# ventmon_t0_4.net
KiCad netlist of a schematic drawn in EAGLE
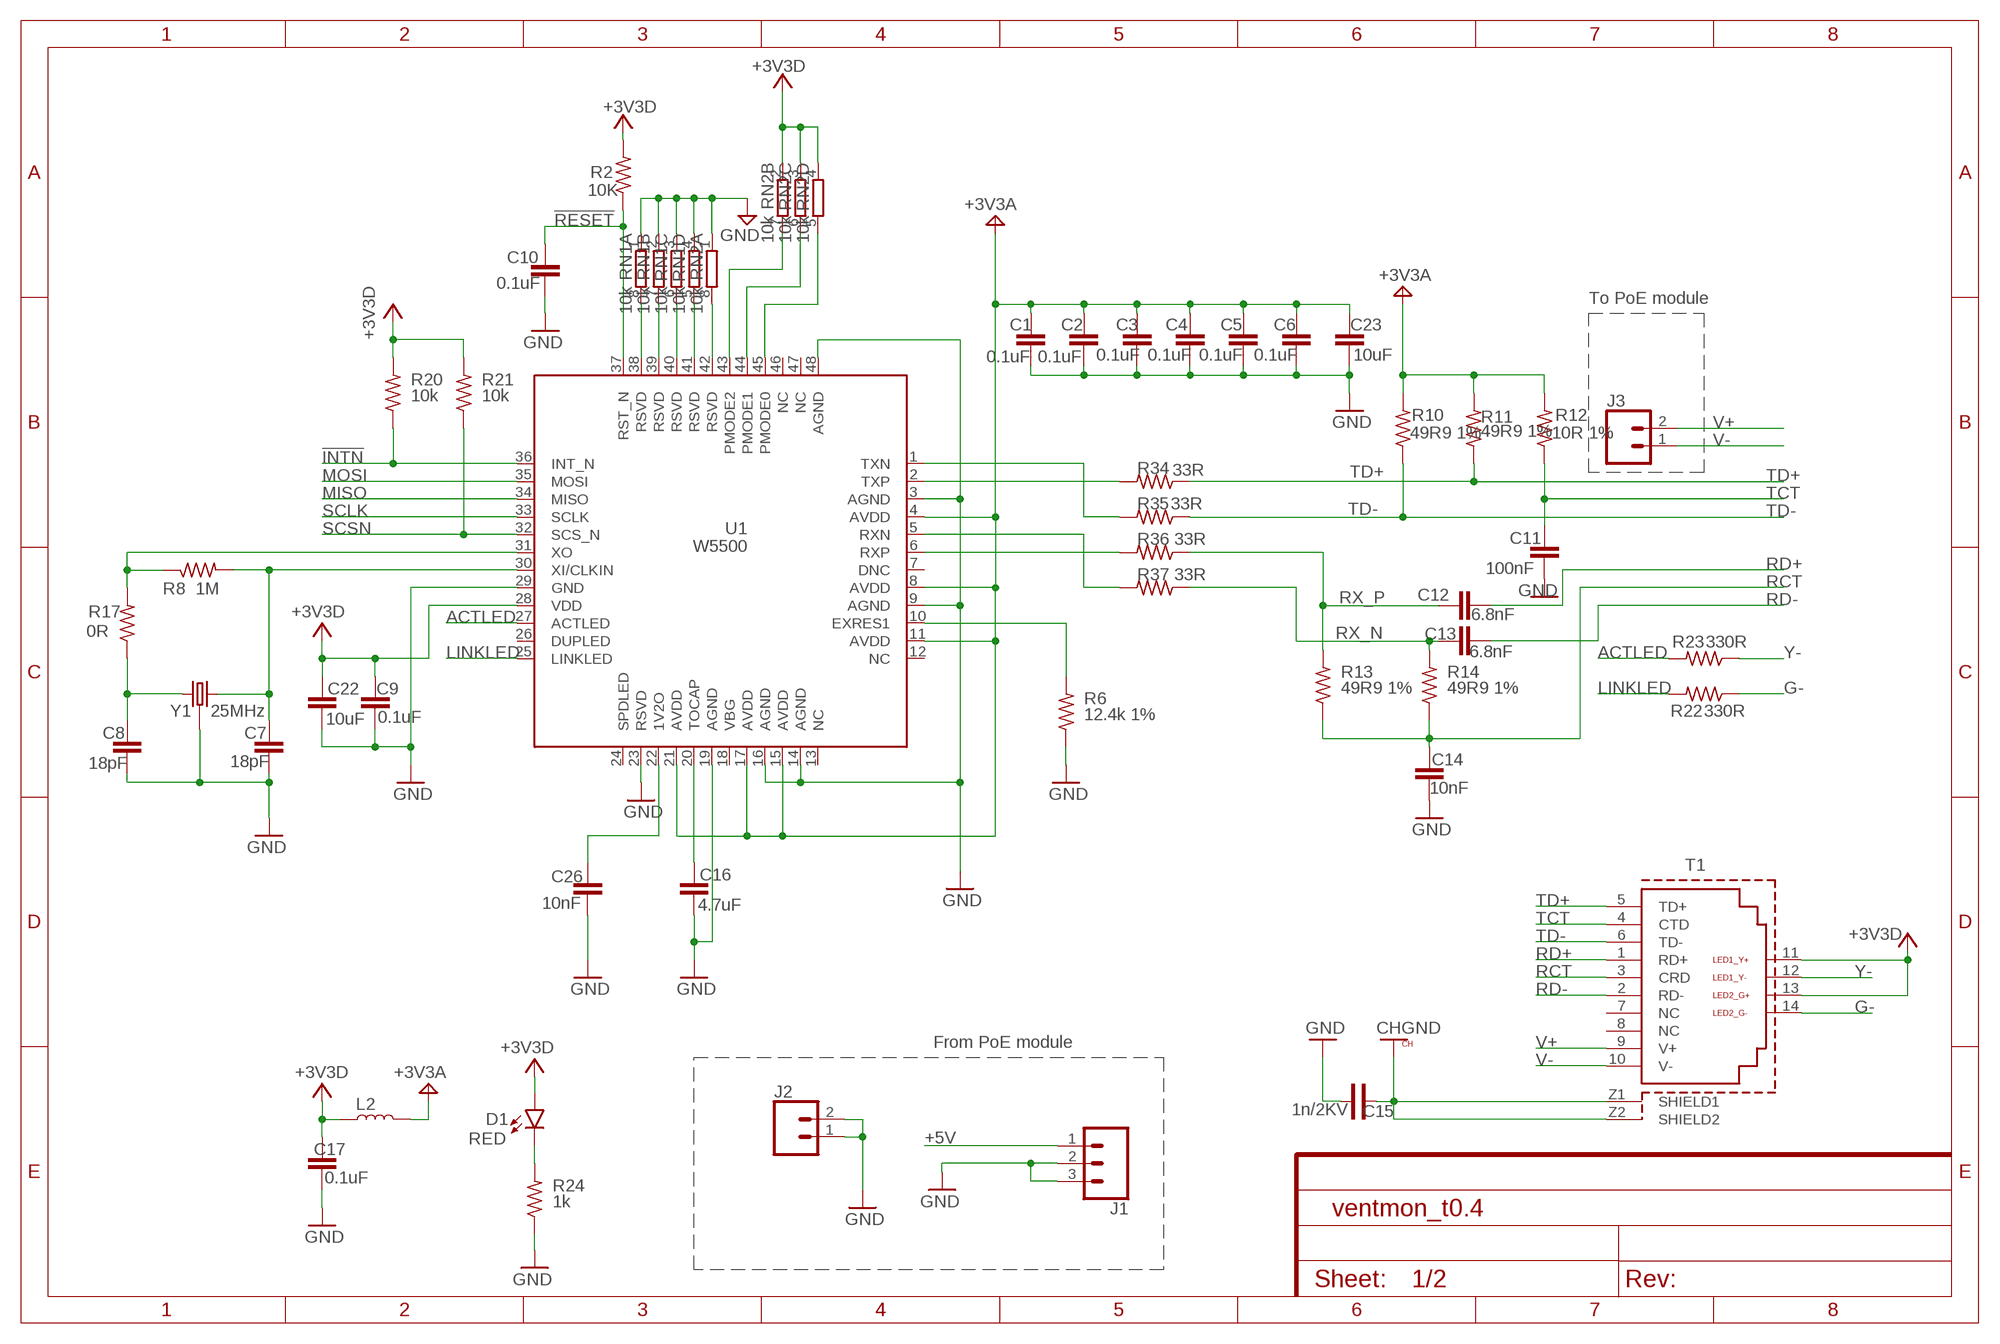
[diagram p0: schematic, sheet 1]
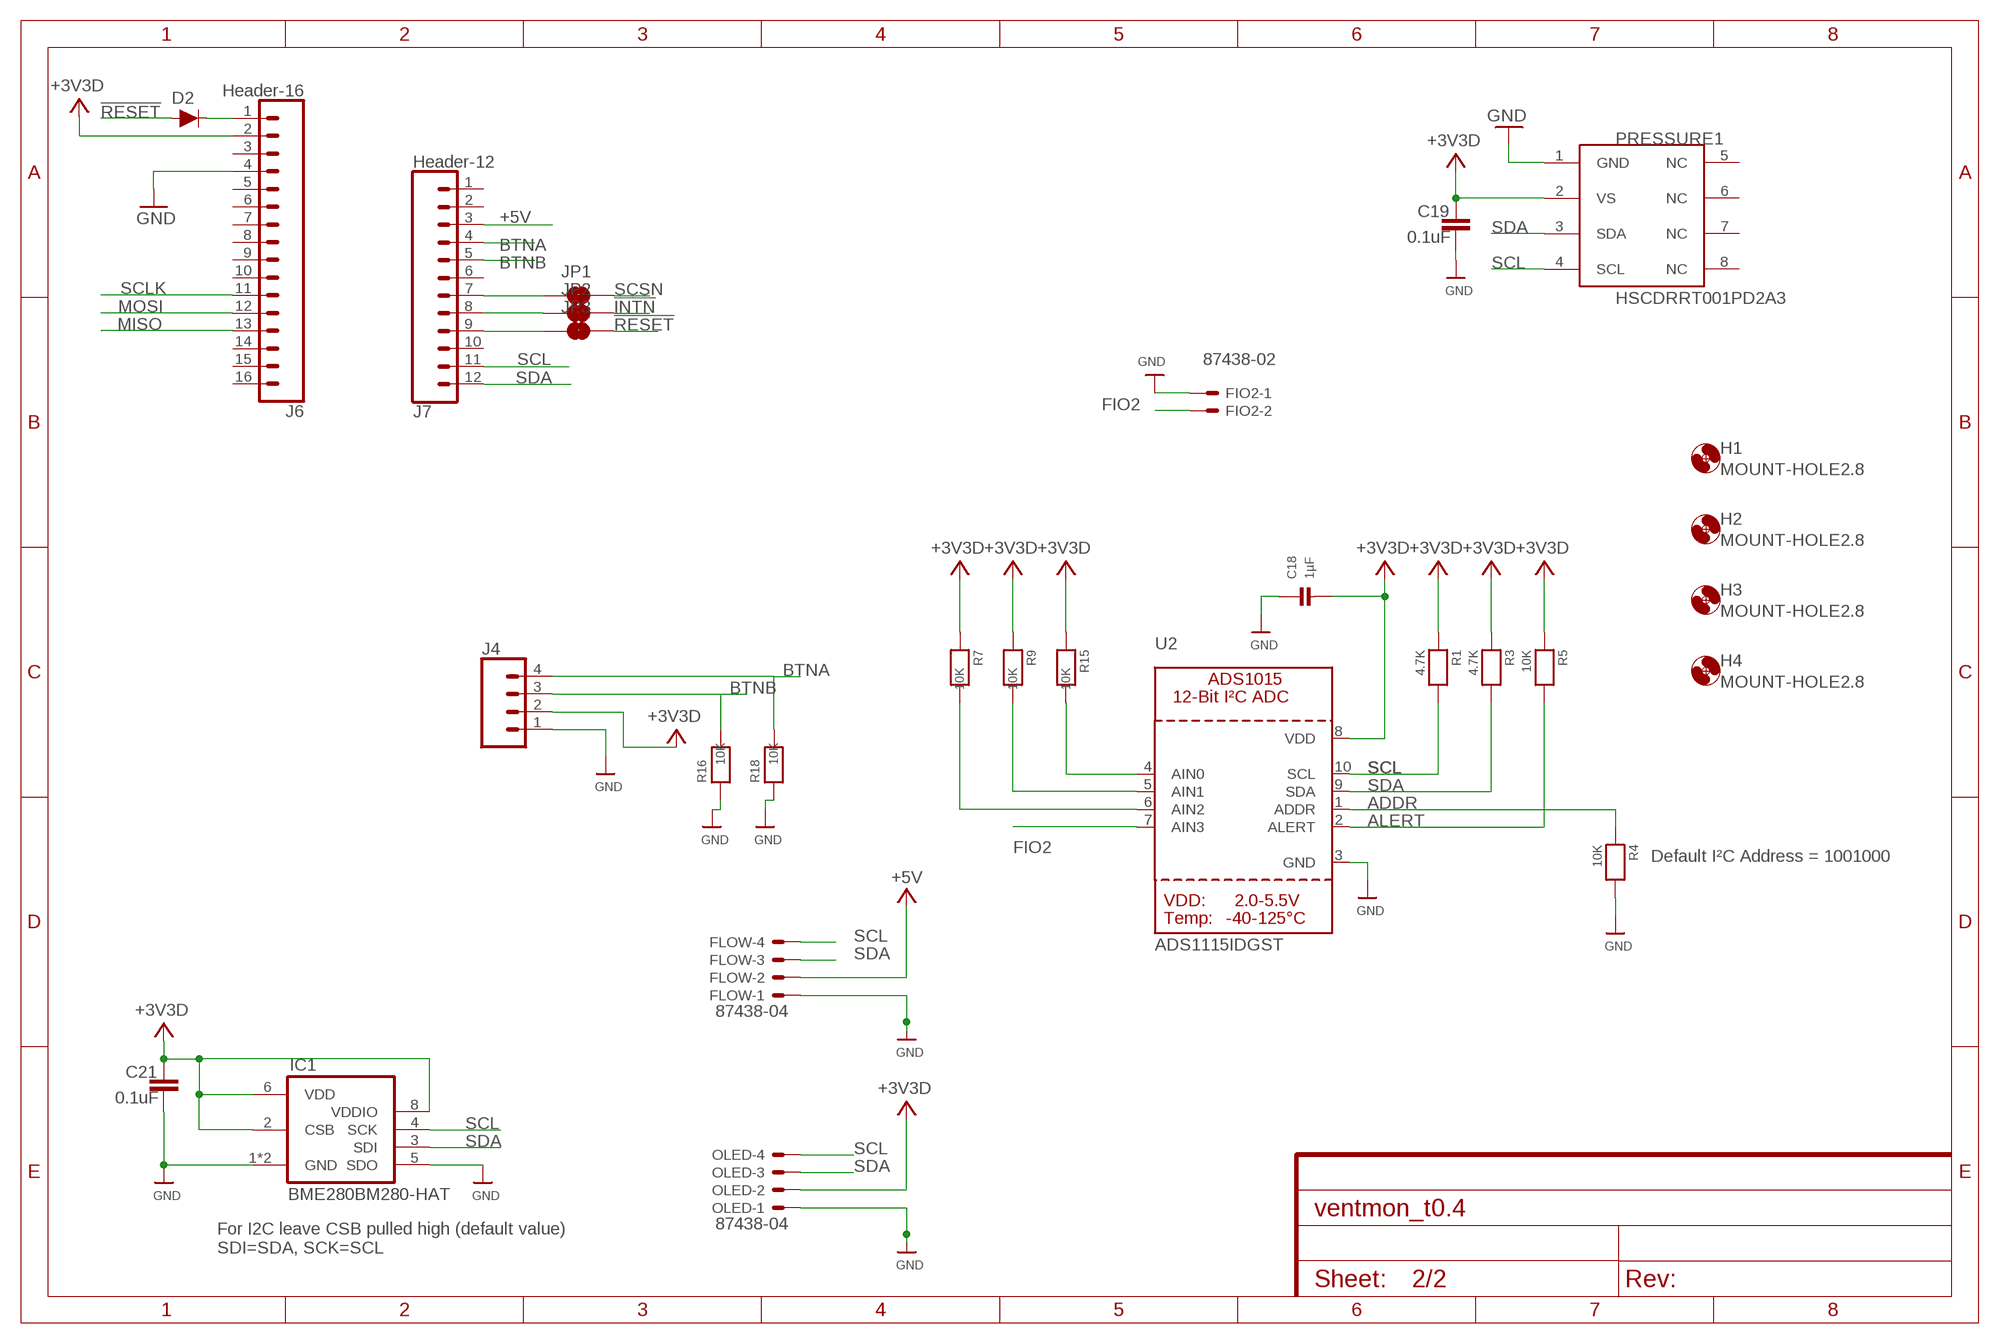
[diagram p1: schematic, sheet 2]

(export (version "E")
  (design (tool "Eeschema 10.0.6"))
  (components
    (comp (ref "C1")
      (value "0.1uF")
      (footprint "eagle-import:C0402_B")
      (libsource (lib "eagle-import") (part "CAP_1"))
    )
    (comp (ref "C2")
      (value "0.1uF")
      (footprint "eagle-import:C0402_B")
      (libsource (lib "eagle-import") (part "CAP_1"))
    )
    (comp (ref "C3")
      (value "0.1uF")
      (footprint "eagle-import:C0402_B")
      (libsource (lib "eagle-import") (part "CAP_1"))
    )
    (comp (ref "C4")
      (value "0.1uF")
      (footprint "eagle-import:C0402_B")
      (libsource (lib "eagle-import") (part "CAP_1"))
    )
    (comp (ref "C5")
      (value "0.1uF")
      (footprint "eagle-import:C0402_B")
      (libsource (lib "eagle-import") (part "CAP_1"))
    )
    (comp (ref "C6")
      (value "0.1uF")
      (footprint "eagle-import:C0402_B")
      (libsource (lib "eagle-import") (part "CAP_1"))
    )
    (comp (ref "C7")
      (value "18pF")
      (footprint "eagle-import:C0402_B")
      (libsource (lib "eagle-import") (part "CAP_1"))
    )
    (comp (ref "C8")
      (value "18pF")
      (footprint "eagle-import:C0402_B")
      (libsource (lib "eagle-import") (part "CAP_1"))
    )
    (comp (ref "C9")
      (value "0.1uF")
      (footprint "eagle-import:C0402_B")
      (libsource (lib "eagle-import") (part "CAP_1"))
    )
    (comp (ref "C10")
      (value "0.1uF")
      (footprint "eagle-import:C0402_B")
      (libsource (lib "eagle-import") (part "CAP_1"))
    )
    (comp (ref "C11")
      (value "100nF")
      (footprint "eagle-import:C0402_B")
      (libsource (lib "eagle-import") (part "CAP_1"))
    )
    (comp (ref "C12")
      (value "6.8nF")
      (footprint "eagle-import:C0402_B")
      (libsource (lib "eagle-import") (part "CAP_1"))
    )
    (comp (ref "C13")
      (value "6.8nF")
      (footprint "eagle-import:C0402_B")
      (libsource (lib "eagle-import") (part "CAP_1"))
    )
    (comp (ref "C14")
      (value "10nF")
      (footprint "eagle-import:C0402_B")
      (libsource (lib "eagle-import") (part "CAP_1"))
    )
    (comp (ref "C15")
      (value "1n/2KV")
      (footprint "eagle-import:C-1808")
      (libsource (lib "eagle-import") (part "C-1808"))
    )
    (comp (ref "C16")
      (value "4.7uF")
      (footprint "eagle-import:0603")
      (libsource (lib "eagle-import") (part "0.18UF-0603-10V-10%"))
    )
    (comp (ref "C17")
      (value "0.1uF")
      (footprint "eagle-import:C0402_B")
      (libsource (lib "eagle-import") (part "CAP_1"))
    )
    (comp (ref "C22")
      (value "10uF")
      (footprint "eagle-import:0603")
      (libsource (lib "eagle-import") (part "0.18UF-0603-10V-10%"))
    )
    (comp (ref "C23")
      (value "10uF")
      (footprint "eagle-import:0603")
      (libsource (lib "eagle-import") (part "0.18UF-0603-10V-10%"))
    )
    (comp (ref "C26")
      (value "10nF")
      (footprint "eagle-import:C0402_B")
      (libsource (lib "eagle-import") (part "CAP_1"))
    )
    (comp (ref "D1")
      (value "RED")
      (footprint "eagle-import:LED-0603")
      (libsource (lib "eagle-import") (part "LED-RED0603"))
    )
    (comp (ref "J1")
      (value "CONN_03")
      (footprint "eagle-import:1X03")
      (libsource (lib "eagle-import") (part "CONN_03"))
    )
    (comp (ref "J2")
      (value "CONN_02")
      (footprint "eagle-import:1X02")
      (libsource (lib "eagle-import") (part "CONN_02"))
    )
    (comp (ref "J3")
      (value "CONN_02")
      (footprint "eagle-import:1X02")
      (libsource (lib "eagle-import") (part "CONN_02"))
    )
    (comp (ref "L2")
      (value "INDUCTOR-0805-3.3UH")
      (footprint "eagle-import:0805")
      (libsource (lib "eagle-import") (part "INDUCTOR-0805-3.3UH"))
    )
    (comp (ref "R2")
      (value "10K")
      (footprint "eagle-import:R0402_B")
      (libsource (lib "eagle-import") (part "R-US_"))
    )
    (comp (ref "R6")
      (value "12.4k 1%")
      (footprint "eagle-import:R0402_B")
      (libsource (lib "eagle-import") (part "R-US_"))
    )
    (comp (ref "R8")
      (value "1M")
      (footprint "eagle-import:R0402_B")
      (libsource (lib "eagle-import") (part "R-US_"))
    )
    (comp (ref "R10")
      (value "49R9 1%")
      (footprint "eagle-import:R0402_B")
      (libsource (lib "eagle-import") (part "R-US_"))
    )
    (comp (ref "R11")
      (value "49R9 1%")
      (footprint "eagle-import:R0402_B")
      (libsource (lib "eagle-import") (part "R-US_"))
    )
    (comp (ref "R12")
      (value "10R 1%")
      (footprint "eagle-import:R0402_B")
      (libsource (lib "eagle-import") (part "R-US_"))
    )
    (comp (ref "R13")
      (value "49R9 1%")
      (footprint "eagle-import:R0402_B")
      (libsource (lib "eagle-import") (part "R-US_"))
    )
    (comp (ref "R14")
      (value "49R9 1%")
      (footprint "eagle-import:R0402_B")
      (libsource (lib "eagle-import") (part "R-US_"))
    )
    (comp (ref "R17")
      (value "0R")
      (footprint "eagle-import:R0402_B")
      (libsource (lib "eagle-import") (part "R-US_"))
    )
    (comp (ref "R20")
      (value "10k")
      (footprint "eagle-import:R0402_B")
      (libsource (lib "eagle-import") (part "R-US_"))
    )
    (comp (ref "R21")
      (value "10k")
      (footprint "eagle-import:R0402_B")
      (libsource (lib "eagle-import") (part "R-US_"))
    )
    (comp (ref "R22")
      (value "330R")
      (footprint "eagle-import:R0402_B")
      (libsource (lib "eagle-import") (part "R-US_"))
    )
    (comp (ref "R23")
      (value "330R")
      (footprint "eagle-import:R0402_B")
      (libsource (lib "eagle-import") (part "R-US_"))
    )
    (comp (ref "R24")
      (value "1k")
      (footprint "eagle-import:R0402_B")
      (libsource (lib "eagle-import") (part "R-US_"))
    )
    (comp (ref "R34")
      (value "33R")
      (footprint "eagle-import:R0402_B")
      (libsource (lib "eagle-import") (part "R-US_"))
    )
    (comp (ref "R35")
      (value "33R")
      (footprint "eagle-import:R0402_B")
      (libsource (lib "eagle-import") (part "R-US_"))
    )
    (comp (ref "R36")
      (value "33R")
      (footprint "eagle-import:R0402_B")
      (libsource (lib "eagle-import") (part "R-US_"))
    )
    (comp (ref "R37")
      (value "33R")
      (footprint "eagle-import:R0402_B")
      (libsource (lib "eagle-import") (part "R-US_"))
    )
    (comp (ref "RN1")
      (value "10k")
      (footprint "eagle-import:4X0402ARV341")
      (libsource (lib "eagle-import") (part "4R-N0402ARV341"))
    )
    (comp (ref "RN2")
      (value "10k")
      (footprint "eagle-import:4X0402ARV341")
      (libsource (lib "eagle-import") (part "4R-N0402ARV341"))
    )
    (comp (ref "T1")
      (value "WE-RJ45_7499210121A")
      (footprint "eagle-import:7499210121A")
      (libsource (lib "eagle-import") (part "WE-RJ45_7499210121A"))
    )
    (comp (ref "U1")
      (value "W5500")
      (footprint "eagle-import:W5500")
      (libsource (lib "eagle-import") (part "W5500"))
    )
    (comp (ref "Y1")
      (value "25MHz")
      (footprint "eagle-import:CRYSTAL-SMD-3.2X2.5MM")
      (libsource (lib "eagle-import") (part "CRYSTAL-GROUNDEDSMD-3.2X2.5"))
    )
    (comp (ref "C18")
      (value "1µF")
      (footprint "eagle-import:0805")
      (libsource (lib "eagle-import") (part "CAP_CERAMIC0805"))
    )
    (comp (ref "C19")
      (value "0.1uF")
      (footprint "eagle-import:C0402_B")
      (libsource (lib "eagle-import") (part "CAP_1"))
    )
    (comp (ref "C21")
      (value "0.1uF")
      (footprint "eagle-import:C0402_B")
      (libsource (lib "eagle-import") (part "CAP_1"))
    )
    (comp (ref "D2")
      (value "DIODE-BAS16J")
      (footprint "eagle-import:SOD-323")
      (libsource (lib "eagle-import") (part "DIODE-BAS16J"))
    )
    (comp (ref "FIO2")
      (value "87438-02")
      (footprint "eagle-import:87438-02")
      (fields (field (name "MF") "MOLEX"))
      (libsource (lib "eagle-import") (part "87438-02"))
    )
    (comp (ref "FLOW")
      (value "87438-04")
      (footprint "eagle-import:87438-04")
      (fields (field (name "MF") "MOLEX"))
      (libsource (lib "eagle-import") (part "87438-04"))
    )
    (comp (ref "H1")
      (value "MOUNT-HOLE2.8")
      (footprint "eagle-import:2,8")
      (libsource (lib "eagle-import") (part "MOUNT-HOLE2.8"))
    )
    (comp (ref "H2")
      (value "MOUNT-HOLE2.8")
      (footprint "eagle-import:2,8")
      (libsource (lib "eagle-import") (part "MOUNT-HOLE2.8"))
    )
    (comp (ref "H3")
      (value "MOUNT-HOLE2.8")
      (footprint "eagle-import:2,8")
      (libsource (lib "eagle-import") (part "MOUNT-HOLE2.8"))
    )
    (comp (ref "H4")
      (value "MOUNT-HOLE2.8")
      (footprint "eagle-import:2,8")
      (libsource (lib "eagle-import") (part "MOUNT-HOLE2.8"))
    )
    (comp (ref "IC1")
      (value "BME280BM280-HAT")
      (footprint "eagle-import:BME280-HAT")
      (libsource (lib "eagle-import") (part "BME280BM280-HAT"))
    )
    (comp (ref "J4")
      (value "CONN_04POLAR")
      (footprint "eagle-import:MOLEX-1X4")
      (libsource (lib "eagle-import") (part "CONN_04POLAR"))
    )
    (comp (ref "J6")
      (value "Header-16")
      (footprint "eagle-import:1X16")
      (libsource (lib "eagle-import") (part "CONN_16"))
    )
    (comp (ref "J7")
      (value "Header-12")
      (footprint "eagle-import:1X12")
      (libsource (lib "eagle-import") (part "CONN_12"))
    )
    (comp (ref "JP1")
      (value "JUMPER-SMT_2_NC_TRACE_NO-SILK")
      (footprint "eagle-import:SMT-JUMPER_2_NC_TRACE_NO-SILK")
      (libsource (lib "eagle-import") (part "JUMPER-SMT_2_NC_TRACE_NO-SILK"))
    )
    (comp (ref "JP2")
      (value "JUMPER-SMT_2_NC_TRACE_NO-SILK")
      (footprint "eagle-import:SMT-JUMPER_2_NC_TRACE_NO-SILK")
      (libsource (lib "eagle-import") (part "JUMPER-SMT_2_NC_TRACE_NO-SILK"))
    )
    (comp (ref "JP3")
      (value "JUMPER-SMT_2_NC_TRACE_NO-SILK")
      (footprint "eagle-import:SMT-JUMPER_2_NC_TRACE_NO-SILK")
      (libsource (lib "eagle-import") (part "JUMPER-SMT_2_NC_TRACE_NO-SILK"))
    )
    (comp (ref "OLED")
      (value "87438-04")
      (footprint "eagle-import:87438-04")
      (fields (field (name "MF") "MOLEX"))
      (libsource (lib "eagle-import") (part "87438-04"))
    )
    (comp (ref "PRESSURE1")
      (value "HSCDRRT001PD2A3")
      (footprint "eagle-import:DIP1330W46P254L1000H616Q8B")
      (libsource (lib "eagle-import") (part "HSCDRRT001PD2A3"))
    )
    (comp (ref "R1")
      (value "4.7K")
      (footprint "eagle-import:0805")
      (libsource (lib "eagle-import") (part "RESISTOR0805"))
    )
    (comp (ref "R3")
      (value "4.7K")
      (footprint "eagle-import:0805")
      (libsource (lib "eagle-import") (part "RESISTOR0805"))
    )
    (comp (ref "R4")
      (value "10K")
      (footprint "eagle-import:0805")
      (libsource (lib "eagle-import") (part "RESISTOR0805"))
    )
    (comp (ref "R5")
      (value "10K")
      (footprint "eagle-import:0805")
      (libsource (lib "eagle-import") (part "RESISTOR0805"))
    )
    (comp (ref "R7")
      (value "10K")
      (footprint "eagle-import:0805")
      (libsource (lib "eagle-import") (part "RESISTOR0805"))
    )
    (comp (ref "R9")
      (value "10K")
      (footprint "eagle-import:0805")
      (libsource (lib "eagle-import") (part "RESISTOR0805"))
    )
    (comp (ref "R15")
      (value "10K")
      (footprint "eagle-import:0805")
      (libsource (lib "eagle-import") (part "RESISTOR0805"))
    )
    (comp (ref "R16")
      (value "10K")
      (footprint "eagle-import:0805")
      (libsource (lib "eagle-import") (part "RESISTOR0805"))
    )
    (comp (ref "R18")
      (value "10K")
      (footprint "eagle-import:0805")
      (libsource (lib "eagle-import") (part "RESISTOR0805"))
    )
    (comp (ref "U2")
      (value "ADS1115IDGST")
      (footprint "eagle-import:MSOP10")
      (libsource (lib "eagle-import") (part "ADC_ADS1015"))
    )
  )
  (nets
    (net (code "1") (name "+3V3") (class "Default")
      (node (ref "C17") (pin "2") (pinfunction "P$2_2") (pintype "passive"))
      (node (ref "C18") (pin "2") (pinfunction "P$2_2") (pintype "passive"))
      (node (ref "C19") (pin "2") (pinfunction "P$2_2") (pintype "passive"))
      (node (ref "C21") (pin "2") (pinfunction "P$2_2") (pintype "passive"))
      (node (ref "C22") (pin "1") (pinfunction "1_1") (pintype "passive"))
      (node (ref "C9") (pin "2") (pinfunction "P$2_2") (pintype "passive"))
      (node (ref "D1") (pin "A") (pinfunction "A_A") (pintype "passive"))
      (node (ref "IC1") (pin "2") (pinfunction "CSB_2") (pintype "input"))
      (node (ref "IC1") (pin "6") (pinfunction "VDD_6") (pintype "power_in"))
      (node (ref "IC1") (pin "8") (pinfunction "VDDIO_8") (pintype "power_in"))
      (node (ref "J4") (pin "2") (pinfunction "2_2") (pintype "passive"))
      (node (ref "J6") (pin "2") (pinfunction "2_2") (pintype "passive"))
      (node (ref "L2") (pin "1") (pinfunction "1_1") (pintype "passive"))
      (node (ref "OLED") (pin "2") (pinfunction "S_2") (pintype "passive"))
      (node (ref "PRESSURE1") (pin "2") (pinfunction "VS_2") (pintype "bidirectional"))
      (node (ref "R1") (pin "1") (pinfunction "1_1") (pintype "passive"))
      (node (ref "R15") (pin "1") (pinfunction "1_1") (pintype "passive"))
      (node (ref "R2") (pin "2") (pinfunction "2_2") (pintype "passive"))
      (node (ref "R20") (pin "2") (pinfunction "2_2") (pintype "passive"))
      (node (ref "R21") (pin "2") (pinfunction "2_2") (pintype "passive"))
      (node (ref "R3") (pin "1") (pinfunction "1_1") (pintype "passive"))
      (node (ref "R5") (pin "1") (pinfunction "1_1") (pintype "passive"))
      (node (ref "R7") (pin "1") (pinfunction "1_1") (pintype "passive"))
      (node (ref "R9") (pin "1") (pinfunction "1_1") (pintype "passive"))
      (node (ref "RN2") (pin "2") (pinfunction "1_2") (pintype "passive"))
      (node (ref "RN2") (pin "3") (pinfunction "1_3") (pintype "passive"))
      (node (ref "RN2") (pin "4") (pinfunction "1_4") (pintype "passive"))
      (node (ref "T1") (pin "11") (pinfunction "LED1_Y+_11") (pintype "passive"))
      (node (ref "T1") (pin "13") (pinfunction "LED2_G+_13") (pintype "passive"))
      (node (ref "U1") (pin "28") (pinfunction "VDD_28") (pintype "passive"))
      (node (ref "U2") (pin "8") (pinfunction "VDD_8") (pintype "bidirectional"))
    )
    (net (code "2") (name "+3V3A") (class "Default")
      (node (ref "C1") (pin "2") (pinfunction "P$2_2") (pintype "passive"))
      (node (ref "C2") (pin "2") (pinfunction "P$2_2") (pintype "passive"))
      (node (ref "C23") (pin "1") (pinfunction "1_1") (pintype "passive"))
      (node (ref "C3") (pin "2") (pinfunction "P$2_2") (pintype "passive"))
      (node (ref "C4") (pin "2") (pinfunction "P$2_2") (pintype "passive"))
      (node (ref "C5") (pin "2") (pinfunction "P$2_2") (pintype "passive"))
      (node (ref "C6") (pin "2") (pinfunction "P$2_2") (pintype "passive"))
      (node (ref "L2") (pin "2") (pinfunction "2_2") (pintype "passive"))
      (node (ref "R10") (pin "2") (pinfunction "2_2") (pintype "passive"))
      (node (ref "R11") (pin "2") (pinfunction "2_2") (pintype "passive"))
      (node (ref "R12") (pin "2") (pinfunction "2_2") (pintype "passive"))
      (node (ref "U1") (pin "11") (pinfunction "AVDD_11") (pintype "passive"))
      (node (ref "U1") (pin "15") (pinfunction "AVDD_15") (pintype "passive"))
      (node (ref "U1") (pin "17") (pinfunction "AVDD_17") (pintype "passive"))
      (node (ref "U1") (pin "21") (pinfunction "AVDD_21") (pintype "passive"))
      (node (ref "U1") (pin "4") (pinfunction "AVDD_4") (pintype "passive"))
      (node (ref "U1") (pin "8") (pinfunction "AVDD_8") (pintype "passive"))
    )
    (net (code "3") (name "+5V") (class "Default")
      (node (ref "FLOW") (pin "2") (pinfunction "S_2") (pintype "passive"))
      (node (ref "J1") (pin "1") (pinfunction "1_1") (pintype "passive"))
      (node (ref "J7") (pin "3") (pinfunction "3_3") (pintype "passive"))
    )
    (net (code "4") (name "ACTLED") (class "Default")
      (node (ref "R23") (pin "2") (pinfunction "2_2") (pintype "passive"))
      (node (ref "U1") (pin "27") (pinfunction "ACTLED_27") (pintype "passive"))
    )
    (net (code "5") (name "ADDR") (class "Default")
      (node (ref "R4") (pin "1") (pinfunction "1_1") (pintype "passive"))
      (node (ref "U2") (pin "1") (pinfunction "ADDR_1") (pintype "bidirectional"))
    )
    (net (code "6") (name "ALERT") (class "Default")
      (node (ref "R5") (pin "2") (pinfunction "2_2") (pintype "passive"))
      (node (ref "U2") (pin "2") (pinfunction "ALERT_2") (pintype "bidirectional"))
    )
    (net (code "7") (name "BTNA") (class "Default")
      (node (ref "J4") (pin "4") (pinfunction "4_4") (pintype "passive"))
      (node (ref "J7") (pin "4") (pinfunction "4_4") (pintype "passive"))
      (node (ref "R18") (pin "2") (pinfunction "2_2") (pintype "passive"))
    )
    (net (code "8") (name "BTNB") (class "Default")
      (node (ref "J4") (pin "3") (pinfunction "3_3") (pintype "passive"))
      (node (ref "J7") (pin "5") (pinfunction "5_5") (pintype "passive"))
      (node (ref "R16") (pin "2") (pinfunction "2_2") (pintype "passive"))
    )
    (net (code "9") (name "CHGND") (class "Default")
      (node (ref "C15") (pin "P$1") (pinfunction "P$1_P$1") (pintype "passive"))
      (node (ref "T1") (pin "Z1") (pinfunction "SHIELD1_Z1") (pintype "power_in"))
      (node (ref "T1") (pin "Z2") (pinfunction "SHIELD2_Z2") (pintype "power_in"))
    )
    (net (code "10") (name "FIO2") (class "Default")
      (node (ref "FIO2") (pin "2") (pinfunction "S_2") (pintype "passive"))
      (node (ref "U2") (pin "7") (pinfunction "AIN3_7") (pintype "bidirectional"))
    )
    (net (code "11") (name "G-") (class "Default")
      (node (ref "R22") (pin "1") (pinfunction "1_1") (pintype "passive"))
      (node (ref "T1") (pin "14") (pinfunction "LED2_G-_14") (pintype "passive"))
    )
    (net (code "12") (name "GND") (class "Default")
      (node (ref "C1") (pin "1") (pinfunction "P$1_1") (pintype "passive"))
      (node (ref "C10") (pin "1") (pinfunction "P$1_1") (pintype "passive"))
      (node (ref "C11") (pin "1") (pinfunction "P$1_1") (pintype "passive"))
      (node (ref "C14") (pin "1") (pinfunction "P$1_1") (pintype "passive"))
      (node (ref "C15") (pin "P$2") (pinfunction "P$2_P$2") (pintype "passive"))
      (node (ref "C16") (pin "2") (pinfunction "2_2") (pintype "passive"))
      (node (ref "C17") (pin "1") (pinfunction "P$1_1") (pintype "passive"))
      (node (ref "C18") (pin "1") (pinfunction "P$1_1") (pintype "passive"))
      (node (ref "C19") (pin "1") (pinfunction "P$1_1") (pintype "passive"))
      (node (ref "C2") (pin "1") (pinfunction "P$1_1") (pintype "passive"))
      (node (ref "C21") (pin "1") (pinfunction "P$1_1") (pintype "passive"))
      (node (ref "C22") (pin "2") (pinfunction "2_2") (pintype "passive"))
      (node (ref "C23") (pin "2") (pinfunction "2_2") (pintype "passive"))
      (node (ref "C26") (pin "1") (pinfunction "P$1_1") (pintype "passive"))
      (node (ref "C3") (pin "1") (pinfunction "P$1_1") (pintype "passive"))
      (node (ref "C4") (pin "1") (pinfunction "P$1_1") (pintype "passive"))
      (node (ref "C5") (pin "1") (pinfunction "P$1_1") (pintype "passive"))
      (node (ref "C6") (pin "1") (pinfunction "P$1_1") (pintype "passive"))
      (node (ref "C7") (pin "1") (pinfunction "P$1_1") (pintype "passive"))
      (node (ref "C8") (pin "1") (pinfunction "P$1_1") (pintype "passive"))
      (node (ref "C9") (pin "1") (pinfunction "P$1_1") (pintype "passive"))
      (node (ref "FIO2") (pin "1") (pinfunction "S_1") (pintype "passive"))
      (node (ref "FLOW") (pin "1") (pinfunction "S_1") (pintype "passive"))
      (node (ref "IC1") (pin "1") (pinfunction "GND_1") (pintype "power_in"))
      (node (ref "IC1") (pin "5") (pinfunction "SDO_5") (pintype "input"))
      (node (ref "IC1") (pin "7") (pinfunction "GND_7") (pintype "power_in"))
      (node (ref "J1") (pin "2") (pinfunction "2_2") (pintype "passive"))
      (node (ref "J1") (pin "3") (pinfunction "3_3") (pintype "passive"))
      (node (ref "J2") (pin "1") (pinfunction "1_1") (pintype "passive"))
      (node (ref "J2") (pin "2") (pinfunction "2_2") (pintype "passive"))
      (node (ref "J4") (pin "1") (pinfunction "1_1") (pintype "passive"))
      (node (ref "J6") (pin "4") (pinfunction "4_4") (pintype "passive"))
      (node (ref "OLED") (pin "1") (pinfunction "S_1") (pintype "passive"))
      (node (ref "PRESSURE1") (pin "1") (pinfunction "GND_1") (pintype "bidirectional"))
      (node (ref "R16") (pin "1") (pinfunction "1_1") (pintype "passive"))
      (node (ref "R18") (pin "1") (pinfunction "1_1") (pintype "passive"))
      (node (ref "R24") (pin "1") (pinfunction "1_1") (pintype "passive"))
      (node (ref "R4") (pin "2") (pinfunction "2_2") (pintype "passive"))
      (node (ref "R6") (pin "1") (pinfunction "1_1") (pintype "passive"))
      (node (ref "RN1") (pin "1") (pinfunction "1_1") (pintype "passive"))
      (node (ref "RN1") (pin "2") (pinfunction "1_2") (pintype "passive"))
      (node (ref "RN1") (pin "3") (pinfunction "1_3") (pintype "passive"))
      (node (ref "RN1") (pin "4") (pinfunction "1_4") (pintype "passive"))
      (node (ref "RN2") (pin "1") (pinfunction "1_1") (pintype "passive"))
      (node (ref "U1") (pin "14") (pinfunction "AGND_14") (pintype "passive"))
      (node (ref "U1") (pin "16") (pinfunction "AGND_16") (pintype "passive"))
      (node (ref "U1") (pin "19") (pinfunction "AGND_19") (pintype "passive"))
      (node (ref "U1") (pin "23") (pinfunction "RSVD_23") (pintype "passive"))
      (node (ref "U1") (pin "29") (pinfunction "GND_29") (pintype "passive"))
      (node (ref "U1") (pin "3") (pinfunction "AGND_3") (pintype "passive"))
      (node (ref "U1") (pin "48") (pinfunction "AGND_48") (pintype "passive"))
      (node (ref "U1") (pin "9") (pinfunction "AGND_9") (pintype "passive"))
      (node (ref "U2") (pin "3") (pinfunction "GND_3") (pintype "bidirectional"))
      (node (ref "Y1") (pin "2") (pinfunction "3_2") (pintype "passive"))
      (node (ref "Y1") (pin "4") (pinfunction "3_4") (pintype "passive"))
    )
    (net (code "13") (name "LINKLED") (class "Default")
      (node (ref "R22") (pin "2") (pinfunction "2_2") (pintype "passive"))
      (node (ref "U1") (pin "25") (pinfunction "LINKLED_25") (pintype "passive"))
    )
    (net (code "14") (name "MISO") (class "Default")
      (node (ref "J6") (pin "13") (pinfunction "13_13") (pintype "passive"))
      (node (ref "U1") (pin "34") (pinfunction "MISO_34") (pintype "passive"))
    )
    (net (code "15") (name "MOSI") (class "Default")
      (node (ref "J6") (pin "12") (pinfunction "12_12") (pintype "passive"))
      (node (ref "U1") (pin "35") (pinfunction "MOSI_35") (pintype "passive"))
    )
    (net (code "16") (name "Net-(C7-P$2)") (class "Default")
      (node (ref "C7") (pin "2") (pinfunction "P$2_2") (pintype "passive"))
      (node (ref "R8") (pin "2") (pinfunction "2_2") (pintype "passive"))
      (node (ref "U1") (pin "30") (pinfunction "XI/CLKIN_30") (pintype "passive"))
      (node (ref "Y1") (pin "3") (pinfunction "2_3") (pintype "passive"))
    )
    (net (code "17") (name "Net-(C8-P$2)") (class "Default")
      (node (ref "C8") (pin "2") (pinfunction "P$2_2") (pintype "passive"))
      (node (ref "R17") (pin "1") (pinfunction "1_1") (pintype "passive"))
      (node (ref "Y1") (pin "1") (pinfunction "1_1") (pintype "passive"))
    )
    (net (code "18") (name "Net-(C26-P$2)") (class "Default")
      (node (ref "C26") (pin "2") (pinfunction "P$2_2") (pintype "passive"))
      (node (ref "U1") (pin "22") (pinfunction "1V2O_22") (pintype "passive"))
    )
    (net (code "19") (name "Net-(D1-PadC)") (class "Default")
      (node (ref "D1") (pin "C") (pinfunction "C_C") (pintype "passive"))
      (node (ref "R24") (pin "2") (pinfunction "2_2") (pintype "passive"))
    )
    (net (code "20") (name "Net-(D2-PadC)") (class "Default")
      (node (ref "D2") (pin "C") (pinfunction "C_C") (pintype "passive"))
      (node (ref "J6") (pin "1") (pinfunction "1_1") (pintype "passive"))
    )
    (net (code "21") (name "Net-(J7-Pad7)") (class "Default")
      (node (ref "J7") (pin "7") (pinfunction "7_7") (pintype "passive"))
      (node (ref "JP1") (pin "1") (pinfunction "1_1") (pintype "passive"))
    )
    (net (code "22") (name "Net-(J7-Pad8)") (class "Default")
      (node (ref "J7") (pin "8") (pinfunction "8_8") (pintype "passive"))
      (node (ref "JP2") (pin "1") (pinfunction "1_1") (pintype "passive"))
    )
    (net (code "23") (name "Net-(J7-Pad9)") (class "Default")
      (node (ref "J7") (pin "9") (pinfunction "9_9") (pintype "passive"))
      (node (ref "JP3") (pin "1") (pinfunction "1_1") (pintype "passive"))
    )
    (net (code "24") (name "Net-(RN1A-2)") (class "Default")
      (node (ref "RN1") (pin "8") (pinfunction "2_8") (pintype "passive"))
      (node (ref "U1") (pin "38") (pinfunction "RSVD_38") (pintype "passive"))
    )
    (net (code "25") (name "Net-(RN1B-2)") (class "Default")
      (node (ref "RN1") (pin "7") (pinfunction "2_7") (pintype "passive"))
      (node (ref "U1") (pin "39") (pinfunction "RSVD_39") (pintype "passive"))
    )
    (net (code "26") (name "Net-(RN1C-2)") (class "Default")
      (node (ref "RN1") (pin "6") (pinfunction "2_6") (pintype "passive"))
      (node (ref "U1") (pin "40") (pinfunction "RSVD_40") (pintype "passive"))
    )
    (net (code "27") (name "Net-(RN1D-2)") (class "Default")
      (node (ref "RN1") (pin "5") (pinfunction "2_5") (pintype "passive"))
      (node (ref "U1") (pin "41") (pinfunction "RSVD_41") (pintype "passive"))
    )
    (net (code "28") (name "Net-(RN2A-2)") (class "Default")
      (node (ref "RN2") (pin "8") (pinfunction "2_8") (pintype "passive"))
      (node (ref "U1") (pin "42") (pinfunction "RSVD_42") (pintype "passive"))
    )
    (net (code "29") (name "Net-(RN2B-2)") (class "Default")
      (node (ref "RN2") (pin "7") (pinfunction "2_7") (pintype "passive"))
      (node (ref "U1") (pin "43") (pinfunction "PMODE2_43") (pintype "passive"))
    )
    (net (code "30") (name "Net-(RN2C-2)") (class "Default")
      (node (ref "RN2") (pin "6") (pinfunction "2_6") (pintype "passive"))
      (node (ref "U1") (pin "44") (pinfunction "PMODE1_44") (pintype "passive"))
    )
    (net (code "31") (name "Net-(RN2D-2)") (class "Default")
      (node (ref "RN2") (pin "5") (pinfunction "2_5") (pintype "passive"))
      (node (ref "U1") (pin "45") (pinfunction "PMODE0_45") (pintype "passive"))
    )
    (net (code "32") (name "Net-(U1-EXRES1)") (class "Default")
      (node (ref "R6") (pin "2") (pinfunction "2_2") (pintype "passive"))
      (node (ref "U1") (pin "10") (pinfunction "EXRES1_10") (pintype "passive"))
    )
    (net (code "33") (name "Net-(U1-RXN)") (class "Default")
      (node (ref "R37") (pin "2") (pinfunction "2_2") (pintype "passive"))
      (node (ref "U1") (pin "5") (pinfunction "RXN_5") (pintype "passive"))
    )
    (net (code "34") (name "Net-(U1-RXP)") (class "Default")
      (node (ref "R36") (pin "2") (pinfunction "2_2") (pintype "passive"))
      (node (ref "U1") (pin "6") (pinfunction "RXP_6") (pintype "passive"))
    )
    (net (code "35") (name "Net-(U1-TOCAP)") (class "Default")
      (node (ref "C16") (pin "1") (pinfunction "1_1") (pintype "passive"))
      (node (ref "U1") (pin "20") (pinfunction "TOCAP_20") (pintype "passive"))
    )
    (net (code "36") (name "Net-(U1-TXN)") (class "Default")
      (node (ref "R35") (pin "2") (pinfunction "2_2") (pintype "passive"))
      (node (ref "U1") (pin "1") (pinfunction "TXN_1") (pintype "passive"))
    )
    (net (code "37") (name "Net-(U1-TXP)") (class "Default")
      (node (ref "R34") (pin "2") (pinfunction "2_2") (pintype "passive"))
      (node (ref "U1") (pin "2") (pinfunction "TXP_2") (pintype "passive"))
    )
    (net (code "38") (name "Net-(U1-XO)") (class "Default")
      (node (ref "R17") (pin "2") (pinfunction "2_2") (pintype "passive"))
      (node (ref "R8") (pin "1") (pinfunction "1_1") (pintype "passive"))
      (node (ref "U1") (pin "31") (pinfunction "XO_31") (pintype "passive"))
    )
    (net (code "39") (name "Net-(U2-AIN0)") (class "Default")
      (node (ref "R15") (pin "2") (pinfunction "2_2") (pintype "passive"))
      (node (ref "U2") (pin "4") (pinfunction "AIN0_4") (pintype "bidirectional"))
    )
    (net (code "40") (name "Net-(U2-AIN1)") (class "Default")
      (node (ref "R9") (pin "2") (pinfunction "2_2") (pintype "passive"))
      (node (ref "U2") (pin "5") (pinfunction "AIN1_5") (pintype "bidirectional"))
    )
    (net (code "41") (name "Net-(U2-AIN2)") (class "Default")
      (node (ref "R7") (pin "2") (pinfunction "2_2") (pintype "passive"))
      (node (ref "U2") (pin "6") (pinfunction "AIN2_6") (pintype "bidirectional"))
    )
    (net (code "42") (name "RCT") (class "Default")
      (node (ref "C14") (pin "2") (pinfunction "P$2_2") (pintype "passive"))
      (node (ref "R13") (pin "1") (pinfunction "1_1") (pintype "passive"))
      (node (ref "R14") (pin "1") (pinfunction "1_1") (pintype "passive"))
      (node (ref "T1") (pin "3") (pinfunction "CRD_3") (pintype "bidirectional"))
    )
    (net (code "43") (name "RD+") (class "Default")
      (node (ref "C12") (pin "2") (pinfunction "P$2_2") (pintype "passive"))
      (node (ref "T1") (pin "1") (pinfunction "RD+_1") (pintype "bidirectional"))
    )
    (net (code "44") (name "RD-") (class "Default")
      (node (ref "C13") (pin "2") (pinfunction "P$2_2") (pintype "passive"))
      (node (ref "T1") (pin "2") (pinfunction "RD-_2") (pintype "bidirectional"))
    )
    (net (code "45") (name "RX_N") (class "Default")
      (node (ref "C13") (pin "1") (pinfunction "P$1_1") (pintype "passive"))
      (node (ref "R14") (pin "2") (pinfunction "2_2") (pintype "passive"))
      (node (ref "R37") (pin "1") (pinfunction "1_1") (pintype "passive"))
    )
    (net (code "46") (name "RX_P") (class "Default")
      (node (ref "C12") (pin "1") (pinfunction "P$1_1") (pintype "passive"))
      (node (ref "R13") (pin "2") (pinfunction "2_2") (pintype "passive"))
      (node (ref "R36") (pin "1") (pinfunction "1_1") (pintype "passive"))
    )
    (net (code "47") (name "SCL") (class "Default")
      (node (ref "FLOW") (pin "4") (pinfunction "S_4") (pintype "passive"))
      (node (ref "IC1") (pin "4") (pinfunction "SCK_4") (pintype "bidirectional"))
      (node (ref "J7") (pin "11") (pinfunction "11_11") (pintype "passive"))
      (node (ref "OLED") (pin "4") (pinfunction "S_4") (pintype "passive"))
      (node (ref "PRESSURE1") (pin "4") (pinfunction "SCL_4") (pintype "bidirectional"))
      (node (ref "R1") (pin "2") (pinfunction "2_2") (pintype "passive"))
      (node (ref "U2") (pin "10") (pinfunction "SCL_10") (pintype "bidirectional"))
    )
    (net (code "48") (name "SCLK") (class "Default")
      (node (ref "J6") (pin "11") (pinfunction "11_11") (pintype "passive"))
      (node (ref "U1") (pin "33") (pinfunction "SCLK_33") (pintype "passive"))
    )
    (net (code "49") (name "SCSN") (class "Default")
      (node (ref "JP1") (pin "2") (pinfunction "2_2") (pintype "passive"))
      (node (ref "R21") (pin "1") (pinfunction "1_1") (pintype "passive"))
      (node (ref "U1") (pin "32") (pinfunction "SCS_N_32") (pintype "passive"))
    )
    (net (code "50") (name "SDA") (class "Default")
      (node (ref "FLOW") (pin "3") (pinfunction "S_3") (pintype "passive"))
      (node (ref "IC1") (pin "3") (pinfunction "SDI_3") (pintype "bidirectional"))
      (node (ref "J7") (pin "12") (pinfunction "12_12") (pintype "passive"))
      (node (ref "OLED") (pin "3") (pinfunction "S_3") (pintype "passive"))
      (node (ref "PRESSURE1") (pin "3") (pinfunction "SDA_3") (pintype "bidirectional"))
      (node (ref "R3") (pin "2") (pinfunction "2_2") (pintype "passive"))
      (node (ref "U2") (pin "9") (pinfunction "SDA_9") (pintype "bidirectional"))
    )
    (net (code "51") (name "TCT") (class "Default")
      (node (ref "C11") (pin "2") (pinfunction "P$2_2") (pintype "passive"))
      (node (ref "R12") (pin "1") (pinfunction "1_1") (pintype "passive"))
      (node (ref "T1") (pin "4") (pinfunction "CTD_4") (pintype "bidirectional"))
    )
    (net (code "52") (name "TD+") (class "Default")
      (node (ref "R11") (pin "1") (pinfunction "1_1") (pintype "passive"))
      (node (ref "R34") (pin "1") (pinfunction "1_1") (pintype "passive"))
      (node (ref "T1") (pin "5") (pinfunction "TD+_5") (pintype "bidirectional"))
    )
    (net (code "53") (name "TD-") (class "Default")
      (node (ref "R10") (pin "1") (pinfunction "1_1") (pintype "passive"))
      (node (ref "R35") (pin "1") (pinfunction "1_1") (pintype "passive"))
      (node (ref "T1") (pin "6") (pinfunction "TD-_6") (pintype "bidirectional"))
    )
    (net (code "54") (name "V+") (class "Default")
      (node (ref "J3") (pin "2") (pinfunction "2_2") (pintype "passive"))
      (node (ref "T1") (pin "9") (pinfunction "V+_9") (pintype "bidirectional"))
    )
    (net (code "55") (name "V-") (class "Default")
      (node (ref "J3") (pin "1") (pinfunction "1_1") (pintype "passive"))
      (node (ref "T1") (pin "10") (pinfunction "V-_10") (pintype "bidirectional"))
    )
    (net (code "56") (name "Y-") (class "Default")
      (node (ref "R23") (pin "1") (pinfunction "1_1") (pintype "passive"))
      (node (ref "T1") (pin "12") (pinfunction "LED1_Y-_12") (pintype "passive"))
    )
    (net (code "57") (name "unconnected-(J6-Pad3)") (class "Default")
      (node (ref "J6") (pin "3") (pinfunction "3_3") (pintype "passive"))
    )
    (net (code "58") (name "unconnected-(J6-Pad5)") (class "Default")
      (node (ref "J6") (pin "5") (pinfunction "5_5") (pintype "passive"))
    )
    (net (code "59") (name "unconnected-(J6-Pad6)") (class "Default")
      (node (ref "J6") (pin "6") (pinfunction "6_6") (pintype "passive"))
    )
    (net (code "60") (name "unconnected-(J6-Pad7)") (class "Default")
      (node (ref "J6") (pin "7") (pinfunction "7_7") (pintype "passive"))
    )
    (net (code "61") (name "unconnected-(J6-Pad8)") (class "Default")
      (node (ref "J6") (pin "8") (pinfunction "8_8") (pintype "passive"))
    )
    (net (code "62") (name "unconnected-(J6-Pad9)") (class "Default")
      (node (ref "J6") (pin "9") (pinfunction "9_9") (pintype "passive"))
    )
    (net (code "63") (name "unconnected-(J6-Pad10)") (class "Default")
      (node (ref "J6") (pin "10") (pinfunction "10_10") (pintype "passive"))
    )
    (net (code "64") (name "unconnected-(J6-Pad14)") (class "Default")
      (node (ref "J6") (pin "14") (pinfunction "14_14") (pintype "passive"))
    )
    (net (code "65") (name "unconnected-(J6-Pad15)") (class "Default")
      (node (ref "J6") (pin "15") (pinfunction "15_15") (pintype "passive"))
    )
    (net (code "66") (name "unconnected-(J6-Pad16)") (class "Default")
      (node (ref "J6") (pin "16") (pinfunction "16_16") (pintype "passive"))
    )
    (net (code "67") (name "unconnected-(J7-Pad1)") (class "Default")
      (node (ref "J7") (pin "1") (pinfunction "1_1") (pintype "passive"))
    )
    (net (code "68") (name "unconnected-(J7-Pad2)") (class "Default")
      (node (ref "J7") (pin "2") (pinfunction "2_2") (pintype "passive"))
    )
    (net (code "69") (name "unconnected-(J7-Pad6)") (class "Default")
      (node (ref "J7") (pin "6") (pinfunction "6_6") (pintype "passive"))
    )
    (net (code "70") (name "unconnected-(J7-Pad10)") (class "Default")
      (node (ref "J7") (pin "10") (pinfunction "10_10") (pintype "passive"))
    )
    (net (code "71") (name "unconnected-(PRESSURE1-NC-Pad5)") (class "Default")
      (node (ref "PRESSURE1") (pin "5") (pinfunction "NC_5") (pintype "bidirectional"))
    )
    (net (code "72") (name "unconnected-(PRESSURE1-NC-Pad6)") (class "Default")
      (node (ref "PRESSURE1") (pin "6") (pinfunction "NC_6") (pintype "bidirectional"))
    )
    (net (code "73") (name "unconnected-(PRESSURE1-NC-Pad7)") (class "Default")
      (node (ref "PRESSURE1") (pin "7") (pinfunction "NC_7") (pintype "bidirectional"))
    )
    (net (code "74") (name "unconnected-(PRESSURE1-NC-Pad8)") (class "Default")
      (node (ref "PRESSURE1") (pin "8") (pinfunction "NC_8") (pintype "bidirectional"))
    )
    (net (code "75") (name "unconnected-(T1-NC-Pad7)") (class "Default")
      (node (ref "T1") (pin "7") (pinfunction "NC_7") (pintype "bidirectional"))
    )
    (net (code "76") (name "unconnected-(T1-NC-Pad8)") (class "Default")
      (node (ref "T1") (pin "8") (pinfunction "NC_8") (pintype "bidirectional"))
    )
    (net (code "77") (name "unconnected-(U1-DNC-Pad7)") (class "Default")
      (node (ref "U1") (pin "7") (pinfunction "DNC_7") (pintype "passive"))
    )
    (net (code "78") (name "unconnected-(U1-DUPLED-Pad26)") (class "Default")
      (node (ref "U1") (pin "26") (pinfunction "DUPLED_26") (pintype "passive"))
    )
    (net (code "79") (name "unconnected-(U1-NC-Pad12)") (class "Default")
      (node (ref "U1") (pin "12") (pinfunction "NC_12") (pintype "passive"))
    )
    (net (code "80") (name "unconnected-(U1-NC-Pad13)") (class "Default")
      (node (ref "U1") (pin "13") (pinfunction "NC_13") (pintype "passive"))
    )
    (net (code "81") (name "unconnected-(U1-NC-Pad46)") (class "Default")
      (node (ref "U1") (pin "46") (pinfunction "NC_46") (pintype "passive"))
    )
    (net (code "82") (name "unconnected-(U1-NC-Pad47)") (class "Default")
      (node (ref "U1") (pin "47") (pinfunction "NC_47") (pintype "passive"))
    )
    (net (code "83") (name "unconnected-(U1-SPDLED-Pad24)") (class "Default")
      (node (ref "U1") (pin "24") (pinfunction "SPDLED_24") (pintype "passive"))
    )
    (net (code "84") (name "unconnected-(U1-VBG-Pad18)") (class "Default")
      (node (ref "U1") (pin "18") (pinfunction "VBG_18") (pintype "passive"))
    )
    (net (code "85") (name "~{INTN}") (class "Default")
      (node (ref "JP2") (pin "2") (pinfunction "2_2") (pintype "passive"))
      (node (ref "R20") (pin "1") (pinfunction "1_1") (pintype "passive"))
      (node (ref "U1") (pin "36") (pinfunction "INT_N_36") (pintype "passive"))
    )
    (net (code "86") (name "~{RESET}") (class "Default")
      (node (ref "C10") (pin "2") (pinfunction "P$2_2") (pintype "passive"))
      (node (ref "D2") (pin "A") (pinfunction "A_A") (pintype "passive"))
      (node (ref "JP3") (pin "2") (pinfunction "2_2") (pintype "passive"))
      (node (ref "R2") (pin "1") (pinfunction "1_1") (pintype "passive"))
      (node (ref "U1") (pin "37") (pinfunction "RST_N_37") (pintype "passive"))
    )
  )
)
